# Buzzer.net
KiCad netlist of a schematic drawn in Altium Designer
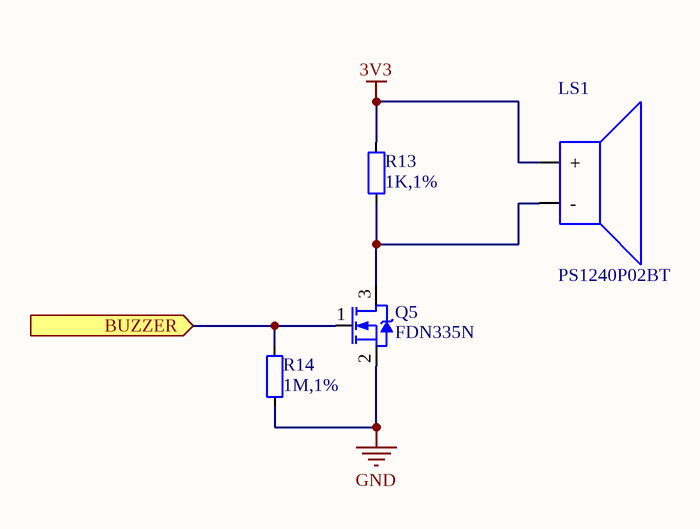
[diagram p0: Buzzer.SchDoc]

(export (version "E")
  (design (tool "Eeschema 10.0.6"))
  (components
    (comp (ref "LS1")
      (value "PS1240P02BT")
      (footprint "SPKR_PS1240P02BT")
      (description "BUZZER PIEZO 4KHZ 12.2MM PC MNT")
      (fields (field (name "MANUFACTURER") "TDK Corporation"))
      (libsource (lib "library") (part "SPEAKER_1"))
    )
    (comp (ref "Q5")
      (value "FDN335N")
      (footprint "SOT95P230X110-3N_SOT23")
      (description "MOSFET N-CH 20V 1.7A SSOT3")
      (fields (field (name "MANUFACTURER") "Fairchild Semiconductor"))
      (libsource (lib "library") (part "MOSFET-N_1"))
    )
    (comp (ref "R13")
      (value "1K,1%")
      (footprint "RESC1608X06N_0603")
      (description "RES 1.00K OHM 1/10W 1% 0603 SMD")
      (fields (field (name "MANUFACTURER") "Yageo") (field (name "POWER") "0.1W"))
      (libsource (lib "library") (part "RESISTOR_1"))
    )
    (comp (ref "R14")
      (value "1M,1%")
      (footprint "RESC1608X06N_0603")
      (description "RES 1.00M OHM 1/10W 1% 0603 SMD")
      (fields (field (name "MANUFACTURER") "Yageo") (field (name "POWER") "0.1W"))
      (libsource (lib "") (part "RESISTOR_1_1"))
    )
  )
  (nets
    (net (code "1") (name "/BUZZER") (class "Default")
      (node (ref "Q5") (pin "1") (pinfunction "G_1") (pintype "passive"))
      (node (ref "R14") (pin "1") (pinfunction "1_1") (pintype "passive"))
    )
    (net (code "2") (name "3V3") (class "Default")
      (node (ref "LS1") (pin "1") (pinfunction "+_1") (pintype "passive"))
      (node (ref "R13") (pin "2") (pinfunction "2_2") (pintype "passive"))
    )
    (net (code "3") (name "GND") (class "Default")
      (node (ref "Q5") (pin "2") (pinfunction "S_2") (pintype "passive"))
      (node (ref "R14") (pin "2") (pinfunction "2_2") (pintype "passive"))
    )
    (net (code "4") (name "Net-(LS1--)") (class "Default")
      (node (ref "LS1") (pin "2") (pinfunction "-_2") (pintype "passive"))
      (node (ref "Q5") (pin "3") (pinfunction "D_3") (pintype "passive"))
      (node (ref "R13") (pin "1") (pinfunction "1_1") (pintype "passive"))
    )
  )
)
